# XYS_1_1_0.net
KiCad netlist of a schematic drawn in EAGLE
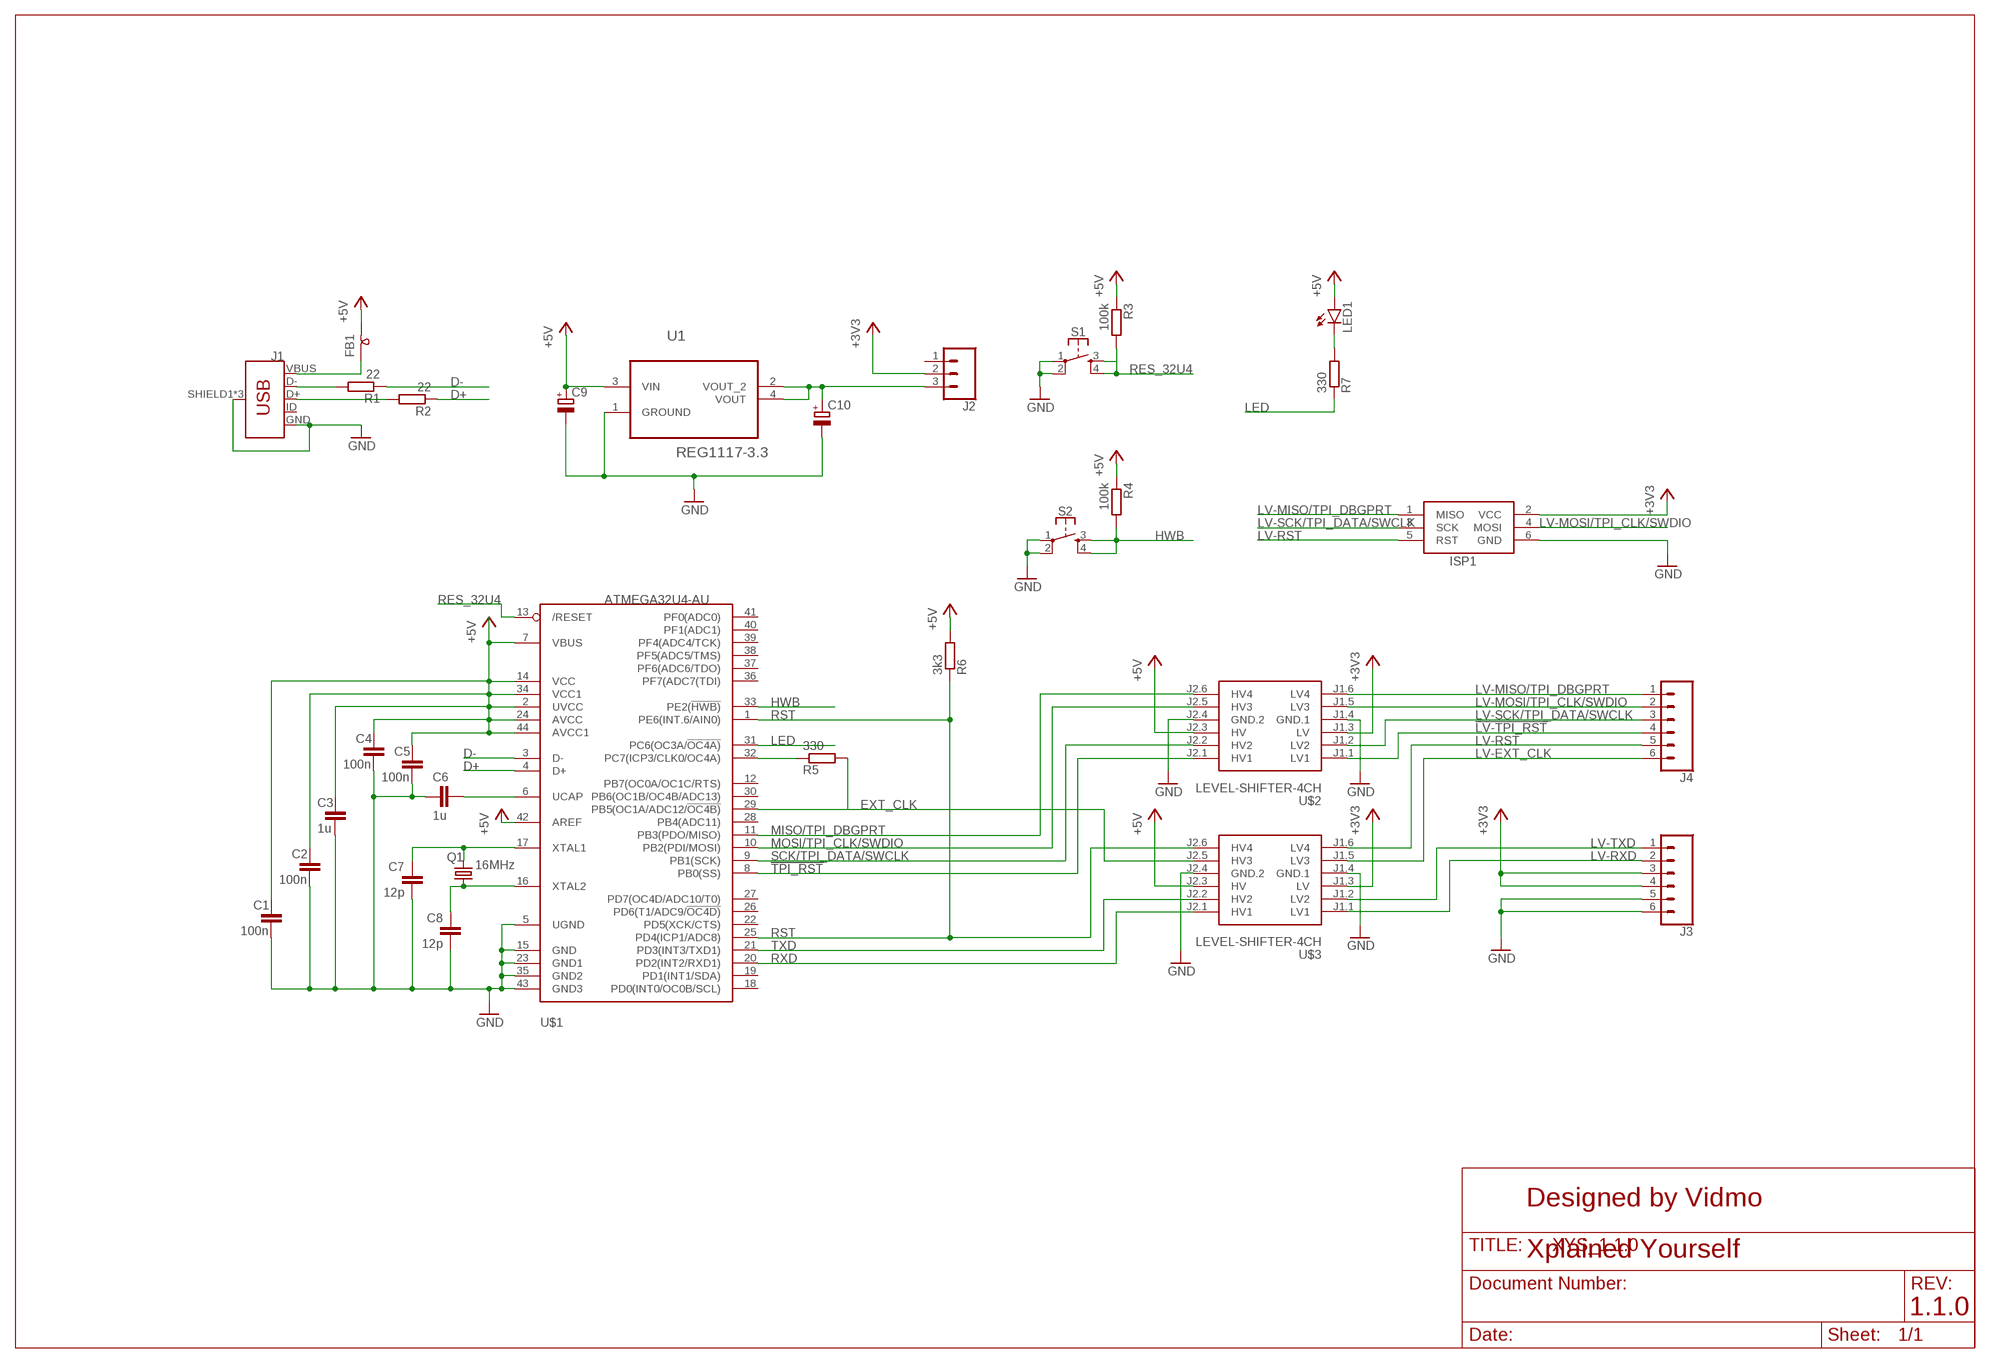
[diagram p0: schematic, sheet 1]

(export (version "E")
  (design (tool "Eeschema 10.0.6"))
  (components
    (comp (ref "C1")
      (value "100n")
      (footprint "eagle-import:C0805K")
      (libsource (lib "eagle-import") (part "C-EUC0805K"))
    )
    (comp (ref "C2")
      (value "100n")
      (footprint "eagle-import:C0805K")
      (libsource (lib "eagle-import") (part "C-EUC0805K"))
    )
    (comp (ref "C3")
      (value "1u")
      (footprint "eagle-import:C0805K")
      (libsource (lib "eagle-import") (part "C-EUC0805K"))
    )
    (comp (ref "C4")
      (value "100n")
      (footprint "eagle-import:C0805K")
      (libsource (lib "eagle-import") (part "C-EUC0805K"))
    )
    (comp (ref "C5")
      (value "100n")
      (footprint "eagle-import:C0805K")
      (libsource (lib "eagle-import") (part "C-EUC0805K"))
    )
    (comp (ref "C6")
      (value "1u")
      (footprint "eagle-import:C0805K")
      (libsource (lib "eagle-import") (part "C-EUC0805K"))
    )
    (comp (ref "C7")
      (value "12p")
      (footprint "eagle-import:C0805K")
      (libsource (lib "eagle-import") (part "C-EUC0805K"))
    )
    (comp (ref "C8")
      (value "12p")
      (footprint "eagle-import:C0805K")
      (libsource (lib "eagle-import") (part "C-EUC0805K"))
    )
    (comp (ref "C9")
      (value "CPOL-EU153CLV-0505")
      (footprint "eagle-import:153CLV-0505")
      (libsource (lib "eagle-import") (part "CPOL-EU153CLV-0505"))
    )
    (comp (ref "C10")
      (value "CPOL-EU153CLV-0505")
      (footprint "eagle-import:153CLV-0505")
      (libsource (lib "eagle-import") (part "CPOL-EU153CLV-0505"))
    )
    (comp (ref "FB1")
      (value "SM-B5")
      (footprint "eagle-import:SM-B5")
      (libsource (lib "eagle-import") (part "SM-B5"))
    )
    (comp (ref "ISP1")
      (value "AVRISP-6")
      (footprint "eagle-import:AVRISP")
      (libsource (lib "eagle-import") (part "AVRISP-6"))
    )
    (comp (ref "J1")
      (value "USB_MICRO-B_FEMALE-SMT")
      (footprint "eagle-import:USB-B-MICRO-SMD")
      (libsource (lib "eagle-import") (part "USB_MICRO-B_FEMALE-SMT"))
    )
    (comp (ref "J2")
      (value "CONN_03")
      (footprint "eagle-import:1X03")
      (libsource (lib "eagle-import") (part "CONN_03"))
    )
    (comp (ref "J3")
      (value "CONN_06LONGPADS")
      (footprint "eagle-import:1X06_LONGPADS")
      (libsource (lib "eagle-import") (part "CONN_06LONGPADS"))
    )
    (comp (ref "J4")
      (value "CONN_06LONGPADS")
      (footprint "eagle-import:1X06_LONGPADS")
      (libsource (lib "eagle-import") (part "CONN_06LONGPADS"))
    )
    (comp (ref "LED1")
      (value "LEDCHIPLED_0805")
      (footprint "eagle-import:CHIPLED_0805")
      (libsource (lib "eagle-import") (part "LEDCHIPLED_0805"))
    )
    (comp (ref "Q1")
      (value "16MHz")
      (footprint "eagle-import:SM49")
      (libsource (lib "eagle-import") (part "CRYSTALSM49"))
    )
    (comp (ref "R1")
      (value "22")
      (footprint "eagle-import:R0805")
      (libsource (lib "eagle-import") (part "R-EU_R0805"))
    )
    (comp (ref "R2")
      (value "22")
      (footprint "eagle-import:R0805")
      (libsource (lib "eagle-import") (part "R-EU_R0805"))
    )
    (comp (ref "R3")
      (value "100k")
      (footprint "eagle-import:R0805")
      (libsource (lib "eagle-import") (part "R-EU_R0805"))
    )
    (comp (ref "R4")
      (value "100k")
      (footprint "eagle-import:R0805")
      (libsource (lib "eagle-import") (part "R-EU_R0805"))
    )
    (comp (ref "R5")
      (value "330")
      (footprint "eagle-import:R0805")
      (libsource (lib "eagle-import") (part "R-EU_R0805"))
    )
    (comp (ref "R6")
      (value "3k3")
      (footprint "eagle-import:R0805")
      (libsource (lib "eagle-import") (part "R-EU_R0805"))
    )
    (comp (ref "R7")
      (value "330")
      (footprint "eagle-import:R0805")
      (libsource (lib "eagle-import") (part "R-EU_R0805"))
    )
    (comp (ref "S1")
      (value "MOMENTARY-SWITCH-SPST-2-SMD-5.2MM")
      (footprint "eagle-import:TACTILE_SWITCH_SMD_5.2MM")
      (libsource (lib "eagle-import") (part "MOMENTARY-SWITCH-SPST-2-SMD-5.2MM"))
    )
    (comp (ref "S2")
      (value "MOMENTARY-SWITCH-SPST-2-SMD-5.2MM")
      (footprint "eagle-import:TACTILE_SWITCH_SMD_5.2MM")
      (libsource (lib "eagle-import") (part "MOMENTARY-SWITCH-SPST-2-SMD-5.2MM"))
    )
    (comp (ref "U$1")
      (value "ATMEGA32U4-AU")
      (footprint "eagle-import:TQFP44")
      (libsource (lib "eagle-import") (part "ATMEGA32U4-AU"))
    )
    (comp (ref "U$2")
      (value "LEVEL-SHIFTER-4CH")
      (footprint "eagle-import:LEVEL-SHIFTER-4CH")
      (libsource (lib "eagle-import") (part "LEVEL-SHIFTER-4CH"))
    )
    (comp (ref "U$3")
      (value "LEVEL-SHIFTER-4CH")
      (footprint "eagle-import:LEVEL-SHIFTER-4CH")
      (libsource (lib "eagle-import") (part "LEVEL-SHIFTER-4CH"))
    )
    (comp (ref "U1")
      (value "REG1117-3.3")
      (footprint "eagle-import:SOT230P700X180-4N")
      (libsource (lib "eagle-import") (part "REG1117-3.3"))
    )
  )
  (nets
    (net (code "1") (name "+3V3") (class "Default")
      (node (ref "ISP1") (pin "2") (pinfunction "VCC_2") (pintype "power_in"))
      (node (ref "J2") (pin "2") (pinfunction "2_2") (pintype "passive"))
      (node (ref "J3") (pin "3") (pinfunction "3_3") (pintype "passive"))
      (node (ref "J3") (pin "4") (pinfunction "4_4") (pintype "passive"))
      (node (ref "U$2") (pin "J1.3") (pinfunction "LV_J1.3") (pintype "power_in"))
      (node (ref "U$3") (pin "J1.3") (pinfunction "LV_J1.3") (pintype "power_in"))
    )
    (net (code "2") (name "+5V") (class "Default")
      (node (ref "C1") (pin "1") (pinfunction "1_1") (pintype "passive"))
      (node (ref "C2") (pin "1") (pinfunction "1_1") (pintype "passive"))
      (node (ref "C3") (pin "1") (pinfunction "1_1") (pintype "passive"))
      (node (ref "C4") (pin "1") (pinfunction "1_1") (pintype "passive"))
      (node (ref "C5") (pin "1") (pinfunction "1_1") (pintype "passive"))
      (node (ref "C9") (pin "+") (pinfunction "+_+") (pintype "passive"))
      (node (ref "FB1") (pin "2") (pinfunction "2_2") (pintype "passive"))
      (node (ref "LED1") (pin "A") (pinfunction "A_A") (pintype "passive"))
      (node (ref "R3") (pin "1") (pinfunction "1_1") (pintype "passive"))
      (node (ref "R4") (pin "1") (pinfunction "1_1") (pintype "passive"))
      (node (ref "R6") (pin "2") (pinfunction "2_2") (pintype "passive"))
      (node (ref "U$1") (pin "14") (pinfunction "VCC_14") (pintype "bidirectional"))
      (node (ref "U$1") (pin "2") (pinfunction "UVCC_2") (pintype "bidirectional"))
      (node (ref "U$1") (pin "24") (pinfunction "AVCC_24") (pintype "bidirectional"))
      (node (ref "U$1") (pin "34") (pinfunction "VCC1_34") (pintype "bidirectional"))
      (node (ref "U$1") (pin "42") (pinfunction "AREF_42") (pintype "bidirectional"))
      (node (ref "U$1") (pin "44") (pinfunction "AVCC1_44") (pintype "bidirectional"))
      (node (ref "U$1") (pin "7") (pinfunction "VBUS_7") (pintype "bidirectional"))
      (node (ref "U$2") (pin "J2.3") (pinfunction "HV_J2.3") (pintype "power_in"))
      (node (ref "U$3") (pin "J2.3") (pinfunction "HV_J2.3") (pintype "power_in"))
      (node (ref "U1") (pin "3") (pinfunction "VIN_3") (pintype "input"))
    )
    (net (code "3") (name "/D+") (class "Default")
      (node (ref "R2") (pin "1") (pinfunction "1_1") (pintype "passive"))
      (node (ref "U$1") (pin "4") (pinfunction "D+_4") (pintype "bidirectional"))
    )
    (net (code "4") (name "/D-") (class "Default")
      (node (ref "R1") (pin "1") (pinfunction "1_1") (pintype "passive"))
      (node (ref "U$1") (pin "3") (pinfunction "D-_3") (pintype "bidirectional"))
    )
    (net (code "5") (name "/EXT_CLK") (class "Default")
      (node (ref "R5") (pin "2") (pinfunction "2_2") (pintype "passive"))
      (node (ref "U$1") (pin "29") (pinfunction "PB5(OC1A/ADC12/~{OC4B})_29") (pintype "bidirectional"))
      (node (ref "U$3") (pin "J2.5") (pinfunction "HV3_J2.5") (pintype "bidirectional"))
    )
    (net (code "6") (name "/HWB") (class "Default")
      (node (ref "R4") (pin "2") (pinfunction "2_2") (pintype "passive"))
      (node (ref "S2") (pin "3") (pinfunction "3_3") (pintype "passive"))
      (node (ref "S2") (pin "4") (pinfunction "4_4") (pintype "passive"))
      (node (ref "U$1") (pin "33") (pinfunction "PE2(~{HWB})_33") (pintype "bidirectional"))
    )
    (net (code "7") (name "/LED") (class "Default")
      (node (ref "R7") (pin "1") (pinfunction "1_1") (pintype "passive"))
      (node (ref "U$1") (pin "31") (pinfunction "PC6(OC3A/~{OC4A})_31") (pintype "bidirectional"))
    )
    (net (code "8") (name "/LV-EXT_CLK") (class "Default")
      (node (ref "J4") (pin "6") (pinfunction "6_6") (pintype "passive"))
      (node (ref "U$3") (pin "J1.5") (pinfunction "LV3_J1.5") (pintype "bidirectional"))
    )
    (net (code "9") (name "/LV-MISO{slash}TPI_DBGPRT") (class "Default")
      (node (ref "ISP1") (pin "1") (pinfunction "MISO_1") (pintype "input"))
      (node (ref "J4") (pin "1") (pinfunction "1_1") (pintype "passive"))
      (node (ref "U$2") (pin "J1.6") (pinfunction "LV4_J1.6") (pintype "bidirectional"))
    )
    (net (code "10") (name "/LV-MOSI{slash}TPI_CLK{slash}SWDIO") (class "Default")
      (node (ref "ISP1") (pin "4") (pinfunction "MOSI_4") (pintype "output"))
      (node (ref "J4") (pin "2") (pinfunction "2_2") (pintype "passive"))
      (node (ref "U$2") (pin "J1.5") (pinfunction "LV3_J1.5") (pintype "bidirectional"))
    )
    (net (code "11") (name "/LV-RST") (class "Default")
      (node (ref "ISP1") (pin "5") (pinfunction "RST_5") (pintype "output"))
      (node (ref "J4") (pin "5") (pinfunction "5_5") (pintype "passive"))
      (node (ref "U$3") (pin "J1.6") (pinfunction "LV4_J1.6") (pintype "bidirectional"))
    )
    (net (code "12") (name "/LV-RXD") (class "Default")
      (node (ref "J3") (pin "2") (pinfunction "2_2") (pintype "passive"))
      (node (ref "U$3") (pin "J1.1") (pinfunction "LV1_J1.1") (pintype "bidirectional"))
    )
    (net (code "13") (name "/LV-SCK{slash}TPI_DATA{slash}SWCLK") (class "Default")
      (node (ref "ISP1") (pin "3") (pinfunction "SCK_3") (pintype "output"))
      (node (ref "J4") (pin "3") (pinfunction "3_3") (pintype "passive"))
      (node (ref "U$2") (pin "J1.2") (pinfunction "LV2_J1.2") (pintype "bidirectional"))
    )
    (net (code "14") (name "/LV-TXD") (class "Default")
      (node (ref "J3") (pin "1") (pinfunction "1_1") (pintype "passive"))
      (node (ref "U$3") (pin "J1.2") (pinfunction "LV2_J1.2") (pintype "bidirectional"))
    )
    (net (code "15") (name "/MISO{slash}TPI_DBGPRT") (class "Default")
      (node (ref "U$1") (pin "11") (pinfunction "PB3(PDO/MISO)_11") (pintype "bidirectional"))
      (node (ref "U$2") (pin "J2.6") (pinfunction "HV4_J2.6") (pintype "bidirectional"))
    )
    (net (code "16") (name "/MOSI{slash}TPI_CLK{slash}SWDIO") (class "Default")
      (node (ref "U$1") (pin "10") (pinfunction "PB2(PDI/MOSI)_10") (pintype "bidirectional"))
      (node (ref "U$2") (pin "J2.5") (pinfunction "HV3_J2.5") (pintype "bidirectional"))
    )
    (net (code "17") (name "/RES_32U4") (class "Default")
      (node (ref "R3") (pin "2") (pinfunction "2_2") (pintype "passive"))
      (node (ref "S1") (pin "3") (pinfunction "3_3") (pintype "passive"))
      (node (ref "S1") (pin "4") (pinfunction "4_4") (pintype "passive"))
      (node (ref "U$1") (pin "13") (pinfunction "/RESET_13") (pintype "bidirectional"))
    )
    (net (code "18") (name "/RST") (class "Default")
      (node (ref "R6") (pin "1") (pinfunction "1_1") (pintype "passive"))
      (node (ref "U$1") (pin "1") (pinfunction "PE6(INT.6/AIN0)_1") (pintype "bidirectional"))
      (node (ref "U$1") (pin "25") (pinfunction "PD4(ICP1/ADC8)_25") (pintype "bidirectional"))
      (node (ref "U$3") (pin "J2.6") (pinfunction "HV4_J2.6") (pintype "bidirectional"))
    )
    (net (code "19") (name "/RXD") (class "Default")
      (node (ref "U$1") (pin "20") (pinfunction "PD2(INT2/RXD1)_20") (pintype "bidirectional"))
      (node (ref "U$3") (pin "J2.1") (pinfunction "HV1_J2.1") (pintype "bidirectional"))
    )
    (net (code "20") (name "/SCK{slash}TPI_DATA{slash}SWCLK") (class "Default")
      (node (ref "U$1") (pin "9") (pinfunction "PB1(SCK)_9") (pintype "bidirectional"))
      (node (ref "U$2") (pin "J2.2") (pinfunction "HV2_J2.2") (pintype "bidirectional"))
    )
    (net (code "21") (name "/TXD") (class "Default")
      (node (ref "U$1") (pin "21") (pinfunction "PD3(INT3/TXD1)_21") (pintype "bidirectional"))
      (node (ref "U$3") (pin "J2.2") (pinfunction "HV2_J2.2") (pintype "bidirectional"))
    )
    (net (code "22") (name "/~{LV-TPI_RST}") (class "Default")
      (node (ref "J4") (pin "4") (pinfunction "4_4") (pintype "passive"))
      (node (ref "U$2") (pin "J1.1") (pinfunction "LV1_J1.1") (pintype "bidirectional"))
    )
    (net (code "23") (name "/~{TPI_RST}") (class "Default")
      (node (ref "U$1") (pin "8") (pinfunction "PB0(SS)_8") (pintype "bidirectional"))
      (node (ref "U$2") (pin "J2.1") (pinfunction "HV1_J2.1") (pintype "bidirectional"))
    )
    (net (code "24") (name "GND") (class "Default")
      (node (ref "C1") (pin "2") (pinfunction "2_2") (pintype "passive"))
      (node (ref "C10") (pin "-") (pinfunction "-_-") (pintype "passive"))
      (node (ref "C2") (pin "2") (pinfunction "2_2") (pintype "passive"))
      (node (ref "C3") (pin "2") (pinfunction "2_2") (pintype "passive"))
      (node (ref "C4") (pin "2") (pinfunction "2_2") (pintype "passive"))
      (node (ref "C5") (pin "2") (pinfunction "2_2") (pintype "passive"))
      (node (ref "C6") (pin "2") (pinfunction "2_2") (pintype "passive"))
      (node (ref "C7") (pin "1") (pinfunction "1_1") (pintype "passive"))
      (node (ref "C8") (pin "1") (pinfunction "1_1") (pintype "passive"))
      (node (ref "C9") (pin "-") (pinfunction "-_-") (pintype "passive"))
      (node (ref "ISP1") (pin "6") (pinfunction "GND_6") (pintype "power_in"))
      (node (ref "J1") (pin "GND") (pinfunction "GND_GND") (pintype "power_in"))
      (node (ref "J1") (pin "SHIELD1") (pinfunction "SHIELD_SHIELD1") (pintype "bidirectional"))
      (node (ref "J1") (pin "SHIELD2") (pinfunction "SHIELD_SHIELD2") (pintype "bidirectional"))
      (node (ref "J1") (pin "SHIELD3") (pinfunction "SHIELD_SHIELD3") (pintype "bidirectional"))
      (node (ref "J3") (pin "5") (pinfunction "5_5") (pintype "passive"))
      (node (ref "J3") (pin "6") (pinfunction "6_6") (pintype "passive"))
      (node (ref "S1") (pin "1") (pinfunction "1_1") (pintype "passive"))
      (node (ref "S1") (pin "2") (pinfunction "2_2") (pintype "passive"))
      (node (ref "S2") (pin "1") (pinfunction "1_1") (pintype "passive"))
      (node (ref "S2") (pin "2") (pinfunction "2_2") (pintype "passive"))
      (node (ref "U$1") (pin "15") (pinfunction "GND_15") (pintype "bidirectional"))
      (node (ref "U$1") (pin "23") (pinfunction "GND1_23") (pintype "bidirectional"))
      (node (ref "U$1") (pin "35") (pinfunction "GND2_35") (pintype "bidirectional"))
      (node (ref "U$1") (pin "43") (pinfunction "GND3_43") (pintype "bidirectional"))
      (node (ref "U$1") (pin "5") (pinfunction "UGND_5") (pintype "bidirectional"))
      (node (ref "U$2") (pin "J1.4") (pinfunction "GND.1_J1.4") (pintype "power_in"))
      (node (ref "U$2") (pin "J2.4") (pinfunction "GND.2_J2.4") (pintype "power_in"))
      (node (ref "U$3") (pin "J1.4") (pinfunction "GND.1_J1.4") (pintype "power_in"))
      (node (ref "U$3") (pin "J2.4") (pinfunction "GND.2_J2.4") (pintype "power_in"))
      (node (ref "U1") (pin "1") (pinfunction "GROUND_1") (pintype "passive"))
    )
    (net (code "25") (name "Net-(FB1-Pad1)") (class "Default")
      (node (ref "FB1") (pin "1") (pinfunction "1_1") (pintype "passive"))
      (node (ref "J1") (pin "VBUS") (pinfunction "VBUS_VBUS") (pintype "power_in"))
    )
    (net (code "26") (name "Net-(J1-PadD+)") (class "Default")
      (node (ref "J1") (pin "D+") (pinfunction "D+_D+") (pintype "bidirectional"))
      (node (ref "R2") (pin "2") (pinfunction "2_2") (pintype "passive"))
    )
    (net (code "27") (name "Net-(J1-PadD-)") (class "Default")
      (node (ref "J1") (pin "D-") (pinfunction "D-_D-") (pintype "bidirectional"))
      (node (ref "R1") (pin "2") (pinfunction "2_2") (pintype "passive"))
    )
    (net (code "28") (name "Net-(LED1-PadC)") (class "Default")
      (node (ref "LED1") (pin "C") (pinfunction "C_C") (pintype "passive"))
      (node (ref "R7") (pin "2") (pinfunction "2_2") (pintype "passive"))
    )
    (net (code "29") (name "Net-(U$1-PC7(ICP3{slash}CLK0{slash}OC4A))") (class "Default")
      (node (ref "R5") (pin "1") (pinfunction "1_1") (pintype "passive"))
      (node (ref "U$1") (pin "32") (pinfunction "PC7(ICP3/CLK0/OC4A)_32") (pintype "bidirectional"))
    )
    (net (code "30") (name "Net-(U$1-UCAP)") (class "Default")
      (node (ref "C6") (pin "1") (pinfunction "1_1") (pintype "passive"))
      (node (ref "U$1") (pin "6") (pinfunction "UCAP_6") (pintype "bidirectional"))
    )
    (net (code "31") (name "Net-(U$1-XTAL1)") (class "Default")
      (node (ref "C7") (pin "2") (pinfunction "2_2") (pintype "passive"))
      (node (ref "Q1") (pin "2") (pinfunction "2_2") (pintype "passive"))
      (node (ref "U$1") (pin "17") (pinfunction "XTAL1_17") (pintype "bidirectional"))
    )
    (net (code "32") (name "Net-(U$1-XTAL2)") (class "Default")
      (node (ref "C8") (pin "2") (pinfunction "2_2") (pintype "passive"))
      (node (ref "Q1") (pin "1") (pinfunction "1_1") (pintype "passive"))
      (node (ref "U$1") (pin "16") (pinfunction "XTAL2_16") (pintype "bidirectional"))
    )
    (net (code "33") (name "Net-(U1-VOUT)") (class "Default")
      (node (ref "C10") (pin "+") (pinfunction "+_+") (pintype "passive"))
      (node (ref "J2") (pin "3") (pinfunction "3_3") (pintype "passive"))
      (node (ref "U1") (pin "2") (pinfunction "VOUT_2_2") (pintype "output"))
      (node (ref "U1") (pin "4") (pinfunction "VOUT_4") (pintype "output"))
    )
    (net (code "34") (name "unconnected-(J1-PadID)") (class "Default")
      (node (ref "J1") (pin "ID") (pinfunction "ID_ID") (pintype "bidirectional"))
    )
    (net (code "35") (name "unconnected-(J2-Pad1)") (class "Default")
      (node (ref "J2") (pin "1") (pinfunction "1_1") (pintype "passive"))
    )
    (net (code "36") (name "unconnected-(U$1-PB4(ADC11)-Pad28)") (class "Default")
      (node (ref "U$1") (pin "28") (pinfunction "PB4(ADC11)_28") (pintype "bidirectional"))
    )
    (net (code "37") (name "unconnected-(U$1-PB6(OC1B{slash}OC4B{slash}ADC13)-Pad30)") (class "Default")
      (node (ref "U$1") (pin "30") (pinfunction "PB6(OC1B/OC4B/ADC13)_30") (pintype "bidirectional"))
    )
    (net (code "38") (name "unconnected-(U$1-PB7(OC0A{slash}OC1C{slash}RTS)-Pad12)") (class "Default")
      (node (ref "U$1") (pin "12") (pinfunction "PB7(OC0A/OC1C/RTS)_12") (pintype "bidirectional"))
    )
    (net (code "39") (name "unconnected-(U$1-PD0(INT0{slash}OC0B{slash}SCL)-Pad18)") (class "Default")
      (node (ref "U$1") (pin "18") (pinfunction "PD0(INT0/OC0B/SCL)_18") (pintype "bidirectional"))
    )
    (net (code "40") (name "unconnected-(U$1-PD1(INT1{slash}SDA)-Pad19)") (class "Default")
      (node (ref "U$1") (pin "19") (pinfunction "PD1(INT1/SDA)_19") (pintype "bidirectional"))
    )
    (net (code "41") (name "unconnected-(U$1-PD5(XCK{slash}CTS)-Pad22)") (class "Default")
      (node (ref "U$1") (pin "22") (pinfunction "PD5(XCK/CTS)_22") (pintype "bidirectional"))
    )
    (net (code "42") (name "unconnected-(U$1-PD6(T1{slash}ADC9{slash}~{OC4D})-Pad26)") (class "Default")
      (node (ref "U$1") (pin "26") (pinfunction "PD6(T1/ADC9/~{OC4D})_26") (pintype "bidirectional"))
    )
    (net (code "43") (name "unconnected-(U$1-PD7(OC4D{slash}ADC10{slash}T0)-Pad27)") (class "Default")
      (node (ref "U$1") (pin "27") (pinfunction "PD7(OC4D/ADC10/T0)_27") (pintype "bidirectional"))
    )
    (net (code "44") (name "unconnected-(U$1-PF0(ADC0)-Pad41)") (class "Default")
      (node (ref "U$1") (pin "41") (pinfunction "PF0(ADC0)_41") (pintype "bidirectional"))
    )
    (net (code "45") (name "unconnected-(U$1-PF1(ADC1)-Pad40)") (class "Default")
      (node (ref "U$1") (pin "40") (pinfunction "PF1(ADC1)_40") (pintype "bidirectional"))
    )
    (net (code "46") (name "unconnected-(U$1-PF4(ADC4{slash}TCK)-Pad39)") (class "Default")
      (node (ref "U$1") (pin "39") (pinfunction "PF4(ADC4/TCK)_39") (pintype "bidirectional"))
    )
    (net (code "47") (name "unconnected-(U$1-PF5(ADC5{slash}TMS)-Pad38)") (class "Default")
      (node (ref "U$1") (pin "38") (pinfunction "PF5(ADC5/TMS)_38") (pintype "bidirectional"))
    )
    (net (code "48") (name "unconnected-(U$1-PF6(ADC6{slash}TDO)-Pad37)") (class "Default")
      (node (ref "U$1") (pin "37") (pinfunction "PF6(ADC6/TDO)_37") (pintype "bidirectional"))
    )
    (net (code "49") (name "unconnected-(U$1-PF7(ADC7(TDI)-Pad36)") (class "Default")
      (node (ref "U$1") (pin "36") (pinfunction "PF7(ADC7(TDI)_36") (pintype "bidirectional"))
    )
  )
)
